# TestDeviceSch_Sheet1.net
KiCad netlist of a schematic drawn in Altium Designer
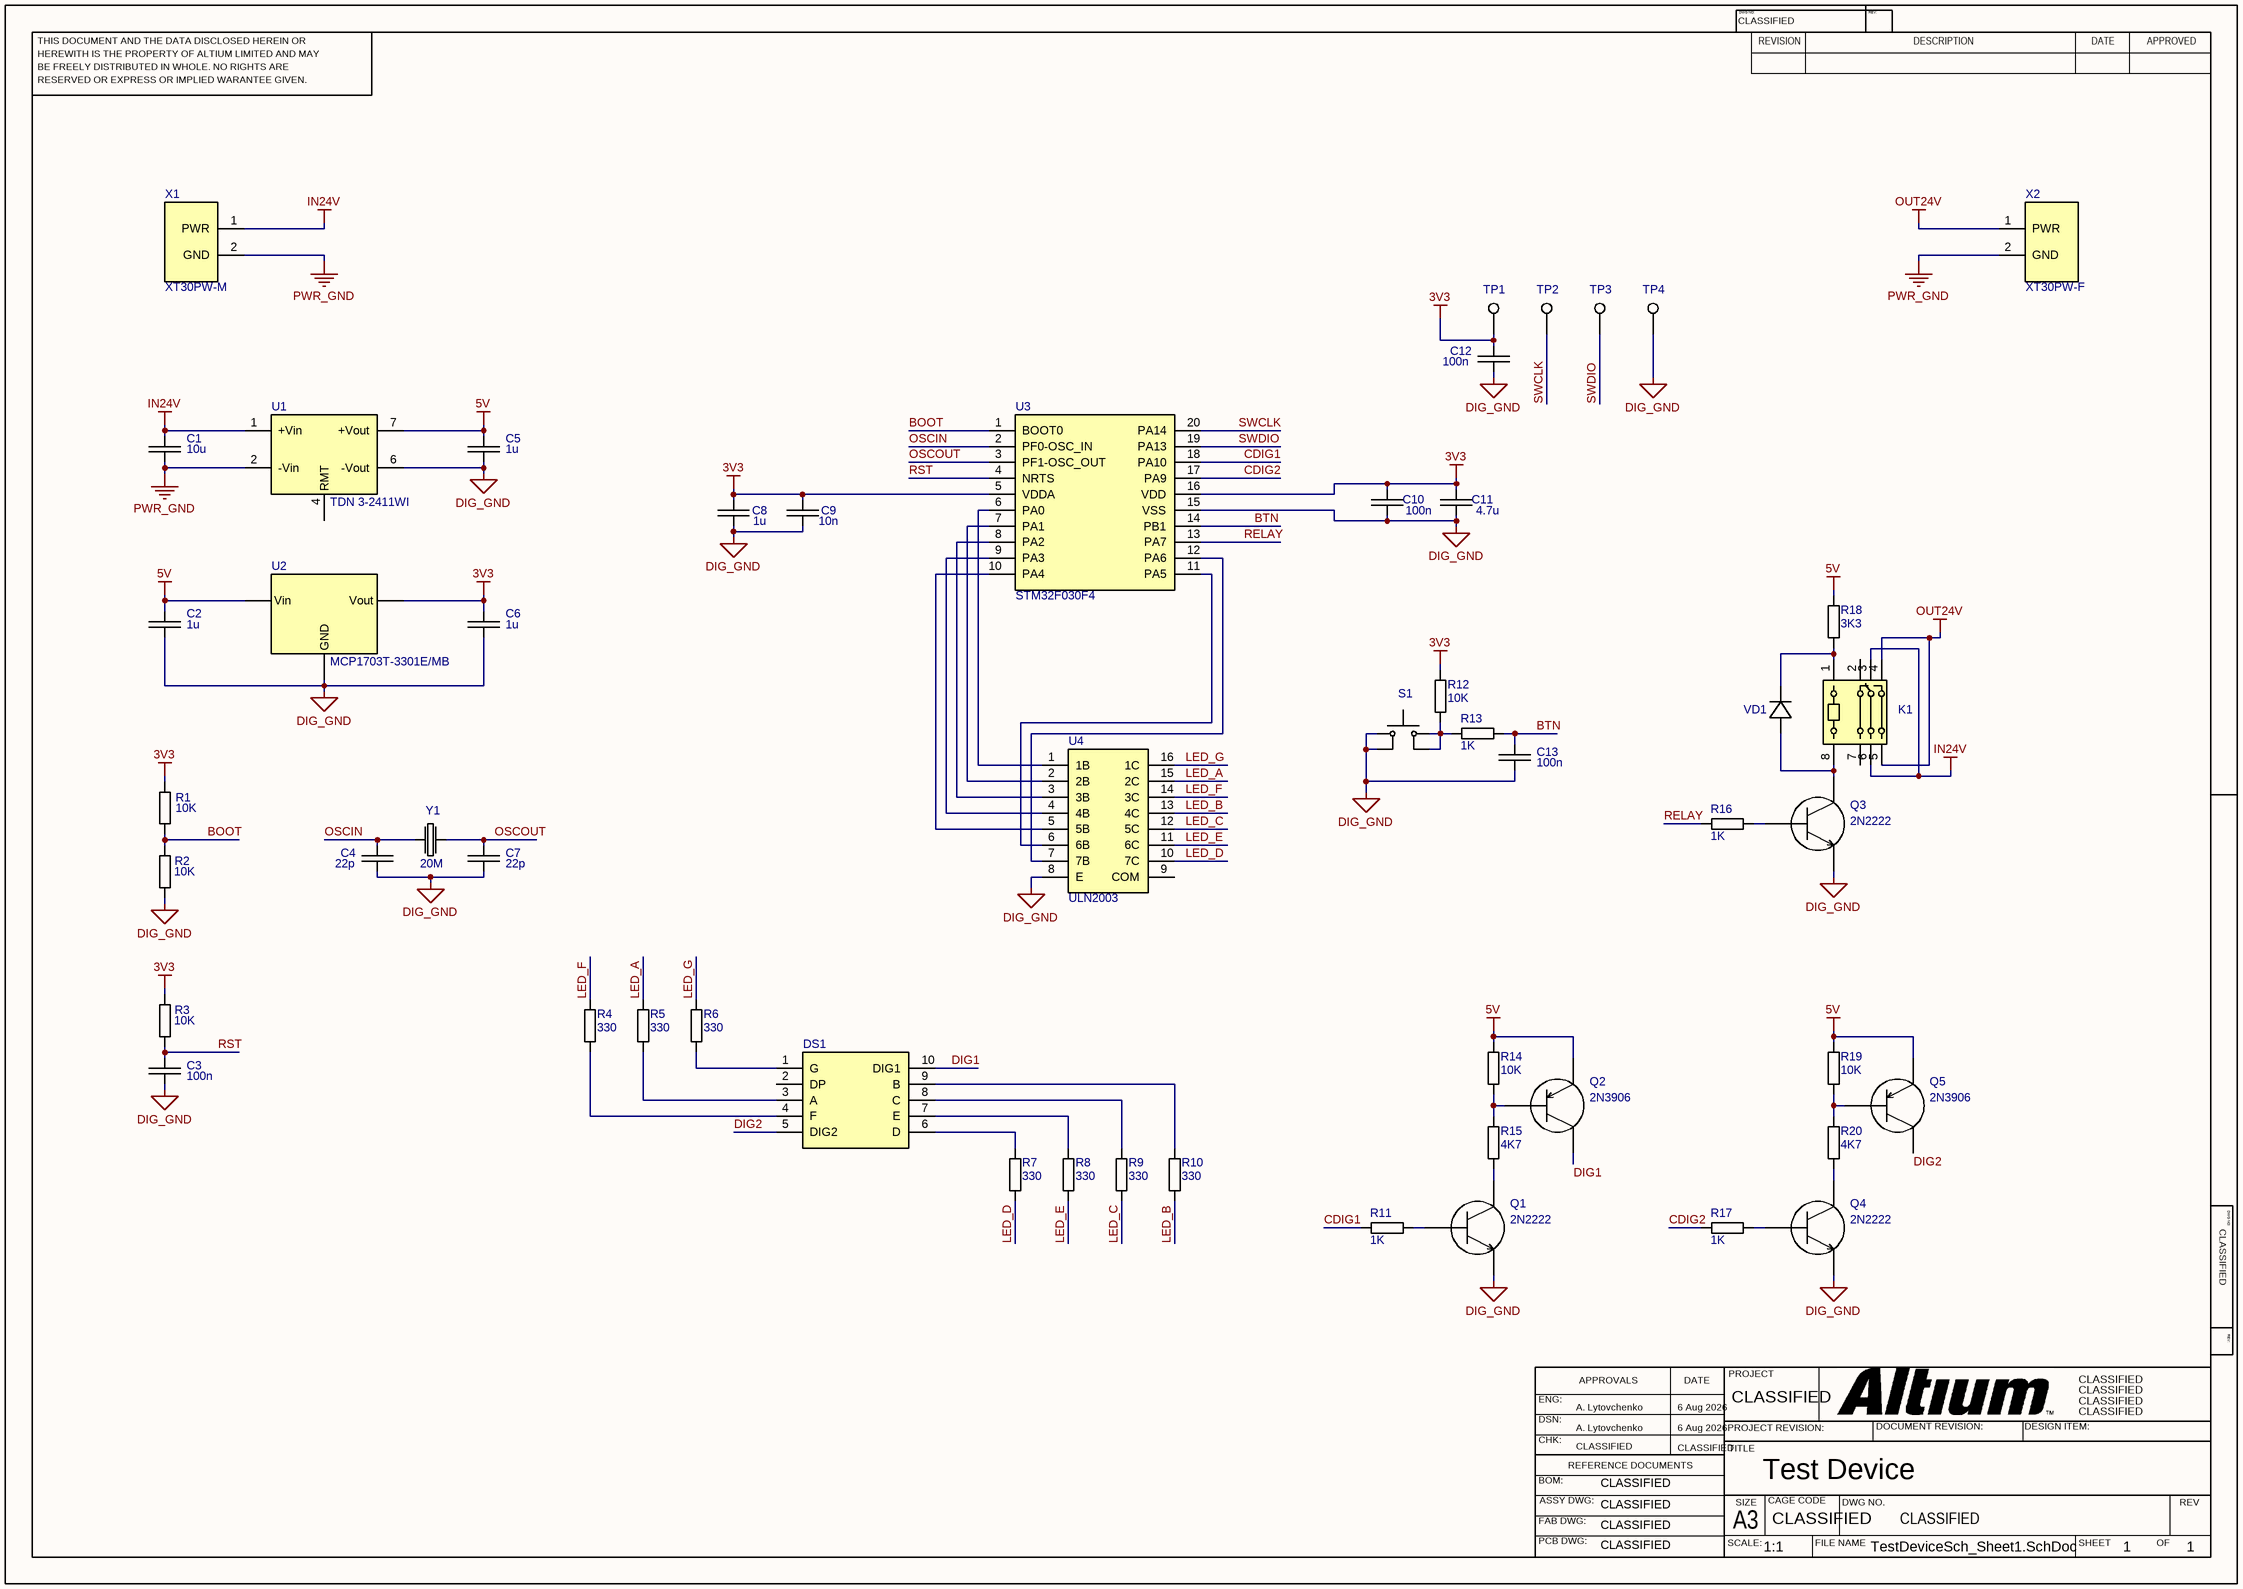
[diagram p0: TestDeviceSch_Sheet1.SchDoc]

(export (version "E")
  (design (tool "Eeschema 10.0.6"))
  (components
    (comp (ref "C1")
      (value "10u")
      (footprint "C0805")
      (fields
        (field (name "MANUFACTURER") "Murata")
        (field (name "PARTNUMBER") "GRM21BR61H106KE43L")
        (field (name "TOLERANCE") "10%")
      )
      (libsource (lib "TestDeviceSchLib") (part "C"))
    )
    (comp (ref "C2")
      (value "1u")
      (footprint "C0805")
      (fields
        (field (name "MANUFACTURER") "Murata")
        (field (name "PARTNUMBER") "GRM21BR71H105KA12L")
        (field (name "TOLERANCE") "5%")
      )
      (libsource (lib "TestDeviceSchLib") (part "C"))
    )
    (comp (ref "C3")
      (value "100n")
      (footprint "C0805")
      (fields
        (field (name "MANUFACTURER") "Murata")
        (field (name "PARTNUMBER") "GRM21BR71H104KA01L")
        (field (name "TOLERANCE") "10%")
      )
      (libsource (lib "TestDeviceSchLib") (part "C"))
    )
    (comp (ref "C4")
      (value "22p")
      (footprint "C0805")
      (fields
        (field (name "MANUFACTURER") "YAGEO")
        (field (name "PARTNUMBER") "CC0805JRNPO9BN220")
        (field (name "TOLERANCE") "5%")
      )
      (libsource (lib "TestDeviceSchLib") (part "C"))
    )
    (comp (ref "C5")
      (value "1u")
      (footprint "C0805")
      (fields
        (field (name "MANUFACTURER") "Murata")
        (field (name "PARTNUMBER") "GRM21BR71H105KA12L")
        (field (name "TOLERANCE") "5%")
      )
      (libsource (lib "TestDeviceSchLib") (part "C"))
    )
    (comp (ref "C6")
      (value "1u")
      (footprint "C0805")
      (fields
        (field (name "MANUFACTURER") "Murata")
        (field (name "PARTNUMBER") "GRM21BR71H105KA12L")
        (field (name "TOLERANCE") "5%")
      )
      (libsource (lib "TestDeviceSchLib") (part "C"))
    )
    (comp (ref "C7")
      (value "22p")
      (footprint "C0805")
      (fields
        (field (name "MANUFACTURER") "YAGEO")
        (field (name "PARTNUMBER") "CC0805JRNPO9BN220")
        (field (name "TOLERANCE") "5%")
      )
      (libsource (lib "TestDeviceSchLib") (part "C"))
    )
    (comp (ref "C8")
      (value "1u")
      (footprint "C0805")
      (fields
        (field (name "MANUFACTURER") "Murata")
        (field (name "PARTNUMBER") "GRM21BR71H105KA12L")
        (field (name "TOLERANCE") "5%")
      )
      (libsource (lib "TestDeviceSchLib") (part "C"))
    )
    (comp (ref "C9")
      (value "10n")
      (footprint "C0805")
      (fields
        (field (name "MANUFACTURER") "Murata")
        (field (name "PARTNUMBER") "GRM2195C1H1103JA01D")
        (field (name "TOLERANCE") "5%")
      )
      (libsource (lib "TestDeviceSchLib") (part "C"))
    )
    (comp (ref "C10")
      (value "100n")
      (footprint "C0805")
      (fields
        (field (name "MANUFACTURER") "Murata")
        (field (name "PARTNUMBER") "GRM21BR71H104KA01L")
        (field (name "TOLERANCE") "10%")
      )
      (libsource (lib "TestDeviceSchLib") (part "C"))
    )
    (comp (ref "C11")
      (value "4.7u")
      (footprint "C0805")
      (fields
        (field (name "MANUFACTURER") "Murata")
        (field (name "PARTNUMBER") "GRM21BR61H475KE51L")
        (field (name "TOLERANCE") "10%")
      )
      (libsource (lib "TestDeviceSchLib") (part "C"))
    )
    (comp (ref "C12")
      (value "100n")
      (footprint "C0805")
      (fields
        (field (name "MANUFACTURER") "Murata")
        (field (name "PARTNUMBER") "GRM21BR71H104KA01L")
        (field (name "TOLERANCE") "10%")
      )
      (libsource (lib "TestDeviceSchLib") (part "C"))
    )
    (comp (ref "C13")
      (value "100n")
      (footprint "C0805")
      (fields
        (field (name "MANUFACTURER") "Murata")
        (field (name "PARTNUMBER") "GRM21BR71H104KA01L")
        (field (name "TOLERANCE") "10%")
      )
      (libsource (lib "TestDeviceSchLib") (part "C"))
    )
    (comp (ref "DS1")
      (value "DISPLAY_7SEG_2DIG_A")
      (footprint "DISPLAY_7SEG_2DIG")
      (description "7 Segment 2 Digit LED Display with Common Anode")
      (fields (field (name "MANUFACTURER") "ARK LED") (field (name "PARTNUMBER") "SN410362"))
      (libsource (lib "TestDeviceSchLib") (part "DISPLAY_7SEG_2DIG_A"))
    )
    (comp (ref "K1")
      (value "JQX-115")
      (footprint "JQX-115F")
      (description "Miniature High Power Relay")
      (fields (field (name "MANUFACTURER") "HONGFA Relay") (field (name "PARTNUMBER") "JQX-115F/0051ZS3AF"))
      (libsource (lib "TestDeviceSchLib") (part "JQX-115"))
    )
    (comp (ref "Q1")
      (value "2N2222")
      (footprint "TO-92")
      (description "Amplifier Bipolar NPN Silicon Transistor")
      (fields (field (name "PARTNUMBER") "P2N2222A") (field (name "MANUFACTURER") "ON Semiconductor"))
      (libsource (lib "TestDeviceSchLib") (part "2N2222"))
    )
    (comp (ref "Q2")
      (value "2N3906")
      (footprint "TO-92")
      (description "General Purpose Bipolar PNP Silicon Transistor")
      (fields (field (name "MANUFACTURER") "ON Semiconductor"))
      (libsource (lib "TestDeviceSchLib") (part "2N3906"))
    )
    (comp (ref "Q3")
      (value "2N2222")
      (footprint "TO-92")
      (description "Amplifier Bipolar NPN Silicon Transistor")
      (fields (field (name "PARTNUMBER") "P2N2222A") (field (name "MANUFACTURER") "ON Semiconductor"))
      (libsource (lib "TestDeviceSchLib") (part "2N2222"))
    )
    (comp (ref "Q4")
      (value "2N2222")
      (footprint "TO-92")
      (description "Amplifier Bipolar NPN Silicon Transistor")
      (fields (field (name "PARTNUMBER") "P2N2222A") (field (name "MANUFACTURER") "ON Semiconductor"))
      (libsource (lib "TestDeviceSchLib") (part "2N2222"))
    )
    (comp (ref "Q5")
      (value "2N3906")
      (footprint "TO-92")
      (description "General Purpose Bipolar PNP Silicon Transistor")
      (fields (field (name "MANUFACTURER") "ON Semiconductor"))
      (libsource (lib "TestDeviceSchLib") (part "2N3906"))
    )
    (comp (ref "R1")
      (value "10K")
      (footprint "R0805")
      (fields
        (field (name "MANUFACTURER") "YAGEO")
        (field (name "TOLERANCE") "5%")
        (field (name "PARTNUMBER") "RC0805JR-0710KL")
      )
      (libsource (lib "TestDeviceSchLib") (part "R"))
    )
    (comp (ref "R2")
      (value "10K")
      (footprint "R0805")
      (fields
        (field (name "MANUFACTURER") "YAGEO")
        (field (name "TOLERANCE") "5%")
        (field (name "PARTNUMBER") "RC0805JR-0710KL")
      )
      (libsource (lib "TestDeviceSchLib") (part "R"))
    )
    (comp (ref "R3")
      (value "10K")
      (footprint "R0805")
      (fields
        (field (name "MANUFACTURER") "YAGEO")
        (field (name "TOLERANCE") "5%")
        (field (name "PARTNUMBER") "RC0805JR-0710KL")
      )
      (libsource (lib "TestDeviceSchLib") (part "R"))
    )
    (comp (ref "R4")
      (value "330")
      (footprint "R0805")
      (fields
        (field (name "MANUFACTURER") "YAGEO")
        (field (name "TOLERANCE") "5%")
        (field (name "PARTNUMBER") "RC0805JR-07330RL")
      )
      (libsource (lib "TestDeviceSchLib") (part "R"))
    )
    (comp (ref "R5")
      (value "330")
      (footprint "R0805")
      (fields
        (field (name "MANUFACTURER") "YAGEO")
        (field (name "TOLERANCE") "5%")
        (field (name "PARTNUMBER") "RC0805JR-07330RL")
      )
      (libsource (lib "TestDeviceSchLib") (part "R"))
    )
    (comp (ref "R6")
      (value "330")
      (footprint "R0805")
      (fields
        (field (name "MANUFACTURER") "YAGEO")
        (field (name "TOLERANCE") "5%")
        (field (name "PARTNUMBER") "RC0805JR-07330RL")
      )
      (libsource (lib "TestDeviceSchLib") (part "R"))
    )
    (comp (ref "R7")
      (value "330")
      (footprint "R0805")
      (fields
        (field (name "MANUFACTURER") "YAGEO")
        (field (name "TOLERANCE") "5%")
        (field (name "PARTNUMBER") "RC0805JR-07330RL")
      )
      (libsource (lib "TestDeviceSchLib") (part "R"))
    )
    (comp (ref "R8")
      (value "330")
      (footprint "R0805")
      (fields
        (field (name "MANUFACTURER") "YAGEO")
        (field (name "TOLERANCE") "5%")
        (field (name "PARTNUMBER") "RC0805JR-07330RL")
      )
      (libsource (lib "TestDeviceSchLib") (part "R"))
    )
    (comp (ref "R9")
      (value "330")
      (footprint "R0805")
      (fields
        (field (name "MANUFACTURER") "YAGEO")
        (field (name "TOLERANCE") "5%")
        (field (name "PARTNUMBER") "RC0805JR-07330RL")
      )
      (libsource (lib "TestDeviceSchLib") (part "R"))
    )
    (comp (ref "R10")
      (value "330")
      (footprint "R0805")
      (fields
        (field (name "MANUFACTURER") "YAGEO")
        (field (name "TOLERANCE") "5%")
        (field (name "PARTNUMBER") "RC0805JR-07330RL")
      )
      (libsource (lib "TestDeviceSchLib") (part "R"))
    )
    (comp (ref "R11")
      (value "1K")
      (footprint "R0805")
      (fields
        (field (name "MANUFACTURER") "YAGEO")
        (field (name "TOLERANCE") "5%")
        (field (name "PARTNUMBER") "RC0805JR-071KL")
      )
      (libsource (lib "TestDeviceSchLib") (part "R"))
    )
    (comp (ref "R12")
      (value "10K")
      (footprint "R0805")
      (fields
        (field (name "MANUFACTURER") "YAGEO")
        (field (name "TOLERANCE") "5%")
        (field (name "PARTNUMBER") "RC0805JR-0710KL")
      )
      (libsource (lib "TestDeviceSchLib") (part "R"))
    )
    (comp (ref "R13")
      (value "1K")
      (footprint "R0805")
      (fields
        (field (name "MANUFACTURER") "YAGEO")
        (field (name "TOLERANCE") "5%")
        (field (name "PARTNUMBER") "RC0805JR-071KL")
      )
      (libsource (lib "TestDeviceSchLib") (part "R"))
    )
    (comp (ref "R14")
      (value "10K")
      (footprint "R0805")
      (fields
        (field (name "MANUFACTURER") "YAGEO")
        (field (name "TOLERANCE") "5%")
        (field (name "PARTNUMBER") "RC0805JR-0710KL")
      )
      (libsource (lib "TestDeviceSchLib") (part "R"))
    )
    (comp (ref "R15")
      (value "4K7")
      (footprint "R0805")
      (fields
        (field (name "MANUFACTURER") "YAGEO")
        (field (name "TOLERANCE") "5%")
        (field (name "PARTNUMBER") "RC0805JR-074K7L")
      )
      (libsource (lib "TestDeviceSchLib") (part "R"))
    )
    (comp (ref "R16")
      (value "1K")
      (footprint "R0805")
      (fields
        (field (name "MANUFACTURER") "YAGEO")
        (field (name "TOLERANCE") "5%")
        (field (name "PARTNUMBER") "RC0805JR-071KL")
      )
      (libsource (lib "TestDeviceSchLib") (part "R"))
    )
    (comp (ref "R17")
      (value "1K")
      (footprint "R0805")
      (fields
        (field (name "MANUFACTURER") "YAGEO")
        (field (name "TOLERANCE") "5%")
        (field (name "PARTNUMBER") "RC0805JR-071KL")
      )
      (libsource (lib "TestDeviceSchLib") (part "R"))
    )
    (comp (ref "R18")
      (value "3K3")
      (footprint "R0805")
      (fields
        (field (name "MANUFACTURER") "YAGEO")
        (field (name "TOLERANCE") "5%")
        (field (name "PARTNUMBER") "RC0805JR-073K3L")
      )
      (libsource (lib "TestDeviceSchLib") (part "R"))
    )
    (comp (ref "R19")
      (value "10K")
      (footprint "R0805")
      (fields
        (field (name "MANUFACTURER") "YAGEO")
        (field (name "TOLERANCE") "5%")
        (field (name "PARTNUMBER") "RC0805JR-0710KL")
      )
      (libsource (lib "TestDeviceSchLib") (part "R"))
    )
    (comp (ref "R20")
      (value "4K7")
      (footprint "R0805")
      (fields
        (field (name "MANUFACTURER") "YAGEO")
        (field (name "TOLERANCE") "5%")
        (field (name "PARTNUMBER") "RC0805JR-074K7L")
      )
      (libsource (lib "TestDeviceSchLib") (part "R"))
    )
    (comp (ref "S1")
      (value "PTS125SJM73SMTR-2")
      (footprint "SMD_BUTTON_SPST_12X12")
      (description "12 mm x 12 mm Tactile Push Button")
      (fields (field (name "MANUFACTURER") "Littelfuse"))
      (libsource (lib "TestDeviceSchLib") (part "PTS125SJM73SMTR-2"))
    )
    (comp (ref "TP1")
      (value "TEST_POINT")
      (footprint "TEST_POINT")
      (libsource (lib "TestDeviceSchLib") (part "TEST_POINT"))
    )
    (comp (ref "TP2")
      (value "TEST_POINT")
      (footprint "TEST_POINT")
      (libsource (lib "TestDeviceSchLib") (part "TEST_POINT"))
    )
    (comp (ref "TP3")
      (value "TEST_POINT")
      (footprint "TEST_POINT")
      (libsource (lib "TestDeviceSchLib") (part "TEST_POINT"))
    )
    (comp (ref "TP4")
      (value "TEST_POINT")
      (footprint "TEST_POINT")
      (libsource (lib "TestDeviceSchLib") (part "TEST_POINT"))
    )
    (comp (ref "U1")
      (value "TDN 3-2411WI")
      (footprint "TDN3WI")
      (fields (field (name "MANUFACTURER") "Traco Power"))
      (libsource (lib "TestDeviceSchLib") (part "TDN_3WI"))
    )
    (comp (ref "U2")
      (value "MCP1703T-3301E/MB")
      (footprint "SOT89-3")
      (description "Low Quiescent Current LDO, 250 mA, 16V")
      (fields (field (name "MANUFACTURER") "Microchip") (field (name "VOLTAGE") "3.3V"))
      (libsource (lib "TestDeviceSchLib") (part "MCP1703"))
    )
    (comp (ref "U3")
      (value "STM32F030F4")
      (footprint "TSSOP-20")
      (fields (field (name "MANUFACTURER") "STMicroelectronics"))
      (libsource (lib "TestDeviceSchLib") (part "STM32F030F4"))
    )
    (comp (ref "U4")
      (value "ULN2003")
      (footprint "SOIC-16")
      (description "High-Voltage, High-Current Darlington Transistor Array")
      (fields (field (name "PARTNUMBER") "ULN2003ADR") (field (name "MANUFACTURER") "Texas Instruments"))
      (libsource (lib "TestDeviceSchLib") (part "ULN2003"))
    )
    (comp (ref "VD1")
      (value "1N4007")
      (footprint "1N4007")
      (description "General Purpose Plastic Rectifier")
      (fields (field (name "MANUFACTURER") "Vishay") (field (name "PARTNUMBER") "1N4007-E3/54"))
      (libsource (lib "TestDeviceSchLib") (part "1N4007"))
    )
    (comp (ref "X1")
      (value "XT30PW-M")
      (footprint "XT30PW-M")
      (fields (field (name "MANUFACTURER") "AMASS"))
      (libsource (lib "TestDeviceSchLib") (part "XT30PW-M"))
    )
    (comp (ref "X2")
      (value "XT30PW-F")
      (footprint "XT30PW-F")
      (fields (field (name "MANUFACTURER") "AMASS"))
      (libsource (lib "TestDeviceSchLib") (part "XT30PW-F"))
    )
    (comp (ref "Y1")
      (value "20M")
      (footprint "XTAL")
      (description "Crystal Oscillator")
      (fields (field (name "MANUFACTURER") "IQD") (field (name "PARTNUMBER") "LF XTAL003185"))
      (libsource (lib "TestDeviceSchLib") (part "XTAL"))
    )
  )
  (nets
    (net (code "1") (name "/BOOT") (class "Default")
      (node (ref "R1") (pin "1") (pinfunction "1_1") (pintype "passive"))
      (node (ref "R2") (pin "2") (pinfunction "2_2") (pintype "passive"))
      (node (ref "U3") (pin "1") (pinfunction "BOOT0_1") (pintype "passive"))
    )
    (net (code "2") (name "/BTN") (class "Default")
      (node (ref "C13") (pin "2") (pinfunction "2_2") (pintype "passive"))
      (node (ref "R13") (pin "1") (pinfunction "1_1") (pintype "passive"))
      (node (ref "U3") (pin "14") (pinfunction "PB1_14") (pintype "passive"))
    )
    (net (code "3") (name "/CDIG1") (class "Default")
      (node (ref "R11") (pin "2") (pinfunction "2_2") (pintype "passive"))
      (node (ref "U3") (pin "18") (pinfunction "PA10_18") (pintype "passive"))
    )
    (net (code "4") (name "/CDIG2") (class "Default")
      (node (ref "R17") (pin "2") (pinfunction "2_2") (pintype "passive"))
      (node (ref "U3") (pin "17") (pinfunction "PA9_17") (pintype "passive"))
    )
    (net (code "5") (name "/DIG1") (class "Default")
      (node (ref "DS1") (pin "10") (pinfunction "DIG1_10") (pintype "passive"))
      (node (ref "Q2") (pin "3") (pinfunction "COLLECTOR_3") (pintype "passive"))
    )
    (net (code "6") (name "/DIG2") (class "Default")
      (node (ref "DS1") (pin "5") (pinfunction "DIG2_5") (pintype "passive"))
      (node (ref "Q5") (pin "3") (pinfunction "COLLECTOR_3") (pintype "passive"))
    )
    (net (code "7") (name "/LED_A") (class "Default")
      (node (ref "R5") (pin "1") (pinfunction "1_1") (pintype "passive"))
      (node (ref "U4") (pin "15") (pinfunction "2C_15") (pintype "passive"))
    )
    (net (code "8") (name "/LED_B") (class "Default")
      (node (ref "R10") (pin "2") (pinfunction "2_2") (pintype "passive"))
      (node (ref "U4") (pin "13") (pinfunction "4C_13") (pintype "passive"))
    )
    (net (code "9") (name "/LED_C") (class "Default")
      (node (ref "R9") (pin "2") (pinfunction "2_2") (pintype "passive"))
      (node (ref "U4") (pin "12") (pinfunction "5C_12") (pintype "passive"))
    )
    (net (code "10") (name "/LED_D") (class "Default")
      (node (ref "R7") (pin "2") (pinfunction "2_2") (pintype "passive"))
      (node (ref "U4") (pin "10") (pinfunction "7C_10") (pintype "passive"))
    )
    (net (code "11") (name "/LED_E") (class "Default")
      (node (ref "R8") (pin "2") (pinfunction "2_2") (pintype "passive"))
      (node (ref "U4") (pin "11") (pinfunction "6C_11") (pintype "passive"))
    )
    (net (code "12") (name "/LED_F") (class "Default")
      (node (ref "R4") (pin "1") (pinfunction "1_1") (pintype "passive"))
      (node (ref "U4") (pin "14") (pinfunction "3C_14") (pintype "passive"))
    )
    (net (code "13") (name "/LED_G") (class "Default")
      (node (ref "R6") (pin "1") (pinfunction "1_1") (pintype "passive"))
      (node (ref "U4") (pin "16") (pinfunction "1C_16") (pintype "passive"))
    )
    (net (code "14") (name "/OSCIN") (class "Default")
      (node (ref "C4") (pin "2") (pinfunction "2_2") (pintype "passive"))
      (node (ref "U3") (pin "2") (pinfunction "PF0-OSC_IN_2") (pintype "passive"))
      (node (ref "Y1") (pin "1") (pinfunction "1_1") (pintype "passive"))
    )
    (net (code "15") (name "/OSCOUT") (class "Default")
      (node (ref "C7") (pin "2") (pinfunction "2_2") (pintype "passive"))
      (node (ref "U3") (pin "3") (pinfunction "PF1-OSC_OUT_3") (pintype "passive"))
      (node (ref "Y1") (pin "2") (pinfunction "2_2") (pintype "passive"))
    )
    (net (code "16") (name "/RELAY") (class "Default")
      (node (ref "R16") (pin "2") (pinfunction "2_2") (pintype "passive"))
      (node (ref "U3") (pin "13") (pinfunction "PA7_13") (pintype "passive"))
    )
    (net (code "17") (name "/RST") (class "Default")
      (node (ref "C3") (pin "2") (pinfunction "2_2") (pintype "passive"))
      (node (ref "R3") (pin "1") (pinfunction "1_1") (pintype "passive"))
      (node (ref "U3") (pin "4") (pinfunction "NRTS_4") (pintype "passive"))
    )
    (net (code "18") (name "/SWCLK") (class "Default")
      (node (ref "TP2") (pin "1") (pinfunction "1_1") (pintype "passive"))
      (node (ref "U3") (pin "20") (pinfunction "PA14_20") (pintype "passive"))
    )
    (net (code "19") (name "/SWDIO") (class "Default")
      (node (ref "TP3") (pin "1") (pinfunction "1_1") (pintype "passive"))
      (node (ref "U3") (pin "19") (pinfunction "PA13_19") (pintype "passive"))
    )
    (net (code "20") (name "3V3") (class "Default")
      (node (ref "C10") (pin "2") (pinfunction "2_2") (pintype "passive"))
      (node (ref "C11") (pin "2") (pinfunction "2_2") (pintype "passive"))
      (node (ref "C12") (pin "2") (pinfunction "2_2") (pintype "passive"))
      (node (ref "C6") (pin "2") (pinfunction "2_2") (pintype "passive"))
      (node (ref "C8") (pin "2") (pinfunction "2_2") (pintype "passive"))
      (node (ref "C9") (pin "2") (pinfunction "2_2") (pintype "passive"))
      (node (ref "R1") (pin "2") (pinfunction "2_2") (pintype "passive"))
      (node (ref "R12") (pin "1") (pinfunction "1_1") (pintype "passive"))
      (node (ref "R3") (pin "2") (pinfunction "2_2") (pintype "passive"))
      (node (ref "TP1") (pin "1") (pinfunction "1_1") (pintype "passive"))
      (node (ref "U2") (pin "3") (pinfunction "Vout_3") (pintype "passive"))
      (node (ref "U3") (pin "16") (pinfunction "VDD_16") (pintype "passive"))
      (node (ref "U3") (pin "5") (pinfunction "VDDA_5") (pintype "passive"))
    )
    (net (code "21") (name "5V") (class "Default")
      (node (ref "C2") (pin "2") (pinfunction "2_2") (pintype "passive"))
      (node (ref "C5") (pin "2") (pinfunction "2_2") (pintype "passive"))
      (node (ref "Q2") (pin "1") (pinfunction "EMITTER_1") (pintype "passive"))
      (node (ref "Q5") (pin "1") (pinfunction "EMITTER_1") (pintype "passive"))
      (node (ref "R14") (pin "2") (pinfunction "2_2") (pintype "passive"))
      (node (ref "R18") (pin "1") (pinfunction "1_1") (pintype "passive"))
      (node (ref "R19") (pin "2") (pinfunction "2_2") (pintype "passive"))
      (node (ref "U1") (pin "7") (pinfunction "+Vout_7") (pintype "passive"))
      (node (ref "U2") (pin "2") (pinfunction "Vin_2") (pintype "passive"))
    )
    (net (code "22") (name "DIG_GND") (class "Default")
      (node (ref "C10") (pin "1") (pinfunction "1_1") (pintype "passive"))
      (node (ref "C11") (pin "1") (pinfunction "1_1") (pintype "passive"))
      (node (ref "C12") (pin "1") (pinfunction "1_1") (pintype "passive"))
      (node (ref "C13") (pin "1") (pinfunction "1_1") (pintype "passive"))
      (node (ref "C2") (pin "1") (pinfunction "1_1") (pintype "passive"))
      (node (ref "C3") (pin "1") (pinfunction "1_1") (pintype "passive"))
      (node (ref "C4") (pin "1") (pinfunction "1_1") (pintype "passive"))
      (node (ref "C5") (pin "1") (pinfunction "1_1") (pintype "passive"))
      (node (ref "C6") (pin "1") (pinfunction "1_1") (pintype "passive"))
      (node (ref "C7") (pin "1") (pinfunction "1_1") (pintype "passive"))
      (node (ref "C8") (pin "1") (pinfunction "1_1") (pintype "passive"))
      (node (ref "C9") (pin "1") (pinfunction "1_1") (pintype "passive"))
      (node (ref "Q1") (pin "3") (pinfunction "EMITTER_3") (pintype "passive"))
      (node (ref "Q3") (pin "3") (pinfunction "EMITTER_3") (pintype "passive"))
      (node (ref "Q4") (pin "3") (pinfunction "EMITTER_3") (pintype "passive"))
      (node (ref "R2") (pin "1") (pinfunction "1_1") (pintype "passive"))
      (node (ref "S1") (pin "1") (pinfunction "1_1") (pintype "passive"))
      (node (ref "S1") (pin "2") (pinfunction "2_2") (pintype "passive"))
      (node (ref "TP4") (pin "1") (pinfunction "1_1") (pintype "passive"))
      (node (ref "U1") (pin "6") (pinfunction "-Vout_6") (pintype "passive"))
      (node (ref "U2") (pin "1") (pinfunction "GND_1") (pintype "passive"))
      (node (ref "U3") (pin "15") (pinfunction "VSS_15") (pintype "passive"))
      (node (ref "U4") (pin "8") (pinfunction "E_8") (pintype "passive"))
    )
    (net (code "23") (name "IN24V") (class "Default")
      (node (ref "C1") (pin "1") (pinfunction "1_1") (pintype "passive"))
      (node (ref "K1") (pin "3") (pinfunction "3_3") (pintype "passive"))
      (node (ref "K1") (pin "6") (pinfunction "6_6") (pintype "passive"))
      (node (ref "U1") (pin "1") (pinfunction "+Vin_1") (pintype "passive"))
      (node (ref "X1") (pin "1") (pinfunction "PWR_1") (pintype "passive"))
    )
    (net (code "24") (name "Net-(DS1-A)") (class "Default")
      (node (ref "DS1") (pin "3") (pinfunction "A_3") (pintype "passive"))
      (node (ref "R5") (pin "2") (pinfunction "2_2") (pintype "passive"))
    )
    (net (code "25") (name "Net-(DS1-B)") (class "Default")
      (node (ref "DS1") (pin "9") (pinfunction "B_9") (pintype "passive"))
      (node (ref "R10") (pin "1") (pinfunction "1_1") (pintype "passive"))
    )
    (net (code "26") (name "Net-(DS1-C)") (class "Default")
      (node (ref "DS1") (pin "8") (pinfunction "C_8") (pintype "passive"))
      (node (ref "R9") (pin "1") (pinfunction "1_1") (pintype "passive"))
    )
    (net (code "27") (name "Net-(DS1-D)") (class "Default")
      (node (ref "DS1") (pin "6") (pinfunction "D_6") (pintype "passive"))
      (node (ref "R7") (pin "1") (pinfunction "1_1") (pintype "passive"))
    )
    (net (code "28") (name "Net-(DS1-E)") (class "Default")
      (node (ref "DS1") (pin "7") (pinfunction "E_7") (pintype "passive"))
      (node (ref "R8") (pin "1") (pinfunction "1_1") (pintype "passive"))
    )
    (net (code "29") (name "Net-(DS1-F)") (class "Default")
      (node (ref "DS1") (pin "4") (pinfunction "F_4") (pintype "passive"))
      (node (ref "R4") (pin "2") (pinfunction "2_2") (pintype "passive"))
    )
    (net (code "30") (name "Net-(DS1-G)") (class "Default")
      (node (ref "DS1") (pin "1") (pinfunction "G_1") (pintype "passive"))
      (node (ref "R6") (pin "2") (pinfunction "2_2") (pintype "passive"))
    )
    (net (code "31") (name "Net-(Q1-BASE)") (class "Default")
      (node (ref "Q1") (pin "2") (pinfunction "BASE_2") (pintype "passive"))
      (node (ref "R11") (pin "1") (pinfunction "1_1") (pintype "passive"))
    )
    (net (code "32") (name "Net-(Q1-COLLECTOR)") (class "Default")
      (node (ref "Q1") (pin "1") (pinfunction "COLLECTOR_1") (pintype "passive"))
      (node (ref "R15") (pin "1") (pinfunction "1_1") (pintype "passive"))
    )
    (net (code "33") (name "Net-(Q2-BASE)") (class "Default")
      (node (ref "Q2") (pin "2") (pinfunction "BASE_2") (pintype "passive"))
      (node (ref "R14") (pin "1") (pinfunction "1_1") (pintype "passive"))
      (node (ref "R15") (pin "2") (pinfunction "2_2") (pintype "passive"))
    )
    (net (code "34") (name "Net-(Q3-BASE)") (class "Default")
      (node (ref "Q3") (pin "2") (pinfunction "BASE_2") (pintype "passive"))
      (node (ref "R16") (pin "1") (pinfunction "1_1") (pintype "passive"))
    )
    (net (code "35") (name "Net-(Q3-COLLECTOR)") (class "Default")
      (node (ref "K1") (pin "8") (pinfunction "8_8") (pintype "passive"))
      (node (ref "Q3") (pin "1") (pinfunction "COLLECTOR_1") (pintype "passive"))
      (node (ref "VD1") (pin "2") (pinfunction "A_2") (pintype "passive"))
    )
    (net (code "36") (name "Net-(Q4-BASE)") (class "Default")
      (node (ref "Q4") (pin "2") (pinfunction "BASE_2") (pintype "passive"))
      (node (ref "R17") (pin "1") (pinfunction "1_1") (pintype "passive"))
    )
    (net (code "37") (name "Net-(Q4-COLLECTOR)") (class "Default")
      (node (ref "Q4") (pin "1") (pinfunction "COLLECTOR_1") (pintype "passive"))
      (node (ref "R20") (pin "1") (pinfunction "1_1") (pintype "passive"))
    )
    (net (code "38") (name "Net-(Q5-BASE)") (class "Default")
      (node (ref "Q5") (pin "2") (pinfunction "BASE_2") (pintype "passive"))
      (node (ref "R19") (pin "1") (pinfunction "1_1") (pintype "passive"))
      (node (ref "R20") (pin "2") (pinfunction "2_2") (pintype "passive"))
    )
    (net (code "39") (name "Net-(R12-Pad2)") (class "Default")
      (node (ref "R12") (pin "2") (pinfunction "2_2") (pintype "passive"))
      (node (ref "R13") (pin "2") (pinfunction "2_2") (pintype "passive"))
      (node (ref "S1") (pin "3") (pinfunction "3_3") (pintype "passive"))
      (node (ref "S1") (pin "4") (pinfunction "4_4") (pintype "passive"))
    )
    (net (code "40") (name "Net-(U3-PA0)") (class "Default")
      (node (ref "U3") (pin "6") (pinfunction "PA0_6") (pintype "passive"))
      (node (ref "U4") (pin "1") (pinfunction "1B_1") (pintype "passive"))
    )
    (net (code "41") (name "Net-(U3-PA1)") (class "Default")
      (node (ref "U3") (pin "7") (pinfunction "PA1_7") (pintype "passive"))
      (node (ref "U4") (pin "2") (pinfunction "2B_2") (pintype "passive"))
    )
    (net (code "42") (name "Net-(U3-PA2)") (class "Default")
      (node (ref "U3") (pin "8") (pinfunction "PA2_8") (pintype "passive"))
      (node (ref "U4") (pin "3") (pinfunction "3B_3") (pintype "passive"))
    )
    (net (code "43") (name "Net-(U3-PA3)") (class "Default")
      (node (ref "U3") (pin "9") (pinfunction "PA3_9") (pintype "passive"))
      (node (ref "U4") (pin "4") (pinfunction "4B_4") (pintype "passive"))
    )
    (net (code "44") (name "Net-(U3-PA4)") (class "Default")
      (node (ref "U3") (pin "10") (pinfunction "PA4_10") (pintype "passive"))
      (node (ref "U4") (pin "5") (pinfunction "5B_5") (pintype "passive"))
    )
    (net (code "45") (name "Net-(U3-PA5)") (class "Default")
      (node (ref "U3") (pin "11") (pinfunction "PA5_11") (pintype "passive"))
      (node (ref "U4") (pin "6") (pinfunction "6B_6") (pintype "passive"))
    )
    (net (code "46") (name "Net-(U3-PA6)") (class "Default")
      (node (ref "U3") (pin "12") (pinfunction "PA6_12") (pintype "passive"))
      (node (ref "U4") (pin "7") (pinfunction "7B_7") (pintype "passive"))
    )
    (net (code "47") (name "Net-(VD1-C)") (class "Default")
      (node (ref "K1") (pin "1") (pinfunction "1_1") (pintype "passive"))
      (node (ref "R18") (pin "2") (pinfunction "2_2") (pintype "passive"))
      (node (ref "VD1") (pin "1") (pinfunction "C_1") (pintype "passive"))
    )
    (net (code "48") (name "OUT24V") (class "Default")
      (node (ref "K1") (pin "4") (pinfunction "4_4") (pintype "passive"))
      (node (ref "K1") (pin "5") (pinfunction "5_5") (pintype "passive"))
      (node (ref "X2") (pin "1") (pinfunction "PWR_1") (pintype "passive"))
    )
    (net (code "49") (name "PWR_GND") (class "Default")
      (node (ref "C1") (pin "2") (pinfunction "2_2") (pintype "passive"))
      (node (ref "U1") (pin "2") (pinfunction "-Vin_2") (pintype "passive"))
      (node (ref "X1") (pin "2") (pinfunction "GND_2") (pintype "passive"))
      (node (ref "X2") (pin "2") (pinfunction "GND_2") (pintype "passive"))
    )
    (net (code "50") (name "unconnected-(DS1-DP-Pad2)") (class "Default")
      (node (ref "DS1") (pin "2") (pinfunction "DP_2") (pintype "passive"))
    )
    (net (code "51") (name "unconnected-(K1-Pad2)") (class "Default")
      (node (ref "K1") (pin "2") (pinfunction "2_2") (pintype "passive"))
    )
    (net (code "52") (name "unconnected-(K1-Pad7)") (class "Default")
      (node (ref "K1") (pin "7") (pinfunction "7_7") (pintype "passive"))
    )
    (net (code "53") (name "unconnected-(U1-RMT-Pad4)") (class "Default")
      (node (ref "U1") (pin "4") (pinfunction "RMT_4") (pintype "passive"))
    )
    (net (code "54") (name "unconnected-(U4-COM-Pad9)") (class "Default")
      (node (ref "U4") (pin "9") (pinfunction "COM_9") (pintype "passive"))
    )
  )
)
